# pmic_mt3406_buck.net
KiCad netlist of a schematic drawn in Altium Designer
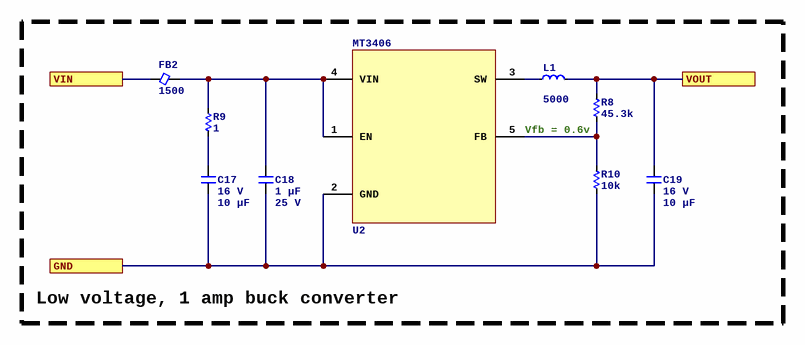
[diagram p0: pmic_mt3406_buck.SchDoc]

(export (version "E")
  (design (tool "Eeschema 10.0.6"))
  (components
    (comp (ref "C17")
      (value "CL21B106KOQNNNE")
      (footprint "C0805")
      (fields
        (field (name "VOLTAGE RATING") "16 V")
        (field (name "CAPACITANCE") "10 µF")
        (field (name "MANUFACTURER") "Samsung Electro-Mechanics")
      )
      (libsource (lib "database") (part "__template_cap"))
    )
    (comp (ref "C18")
      (value "CL10B105KA8NNNC")
      (footprint "C0603")
      (fields
        (field (name "CAPACITANCE") "1 µF")
        (field (name "MANUFACTURER") "Samsung Electro-Mechanics")
        (field (name "VOLTAGE RATING") "25 V")
      )
      (libsource (lib "database") (part "__template_cap"))
    )
    (comp (ref "C19")
      (value "CL21B106KOQNNNE")
      (footprint "C0805")
      (fields
        (field (name "VOLTAGE RATING") "16 V")
        (field (name "CAPACITANCE") "10 µF")
        (field (name "MANUFACTURER") "Samsung Electro-Mechanics")
      )
      (libsource (lib "database") (part "__template_cap"))
    )
    (comp (ref "FB2")
      (value "MPZ2012S102AT000")
      (footprint "FB0805")
      (fields (field (name "CURRENT RATING (MA)") "1500") (field (name "MANUFACTURER") "TDK"))
      (libsource (lib "database") (part "__template_fb"))
    )
    (comp (ref "L1")
      (value "FTC404020S4R7MGCA")
      (footprint "SMD-4.1x4.1x2.0")
      (description "4.7 µH SMD power inductor")
      (fields (field (name "MANUFACTURER") "cjiang") (field (name "CURRENT RATING (MA)") "5000"))
      (libsource (lib "database") (part "__template_inductor"))
    )
    (comp (ref "R8")
      (value "45.3k")
      (footprint "R0402")
      (fields
        (field (name "TOLERANCE") "1%")
        (field (name "MANUFACTURER PART NUMBER") "FRC0402F4532TS")
        (field (name "MANUFACTURER") "FOJAN")
      )
      (libsource (lib "database") (part "__template_resistor"))
    )
    (comp (ref "R9")
      (value "1")
      (footprint "R0402")
      (fields
        (field (name "TOLERANCE") "1%")
        (field (name "MANUFACTURER PART NUMBER") "CRCW04021R00FKEDC")
        (field (name "MANUFACTURER") "Vishay Intertech")
      )
      (libsource (lib "database") (part "__template_resistor"))
    )
    (comp (ref "R10")
      (value "10k")
      (footprint "R0402")
      (fields
        (field (name "TOLERANCE") "1%")
        (field (name "MANUFACTURER PART NUMBER") "0402WGF1002TCE")
        (field (name "MANUFACTURER") "UNI-ROYAL(Uniroyal Elec)")
      )
      (libsource (lib "database") (part "__template_resistor"))
    )
    (comp (ref "U2")
      (value "MT3406")
      (footprint "5SOT23")
      (fields (field (name "MANUFACTURER") "XI'AN Aerosemi Tech"))
      (libsource (lib "database") (part "MT3406"))
    )
  )
  (nets
    (net (code "1") (name "/GND") (class "Default")
      (node (ref "C17") (pin "2") (pintype "passive"))
      (node (ref "C18") (pin "2") (pintype "passive"))
      (node (ref "C19") (pin "2") (pintype "passive"))
      (node (ref "R10") (pin "2") (pintype "passive"))
      (node (ref "U2") (pin "2") (pinfunction "GND_2") (pintype "passive"))
    )
    (net (code "2") (name "/VIN") (class "Default") (node (ref "FB2") (pin "1") (pintype "passive")))
    (net (code "3") (name "/VOUT") (class "Default")
      (node (ref "C19") (pin "1") (pintype "passive"))
      (node (ref "L1") (pin "2") (pintype "passive"))
      (node (ref "R8") (pin "1") (pintype "passive"))
    )
    (net (code "4") (name "Net-(C17-Pad1)") (class "Default")
      (node (ref "C17") (pin "1") (pintype "passive"))
      (node (ref "R9") (pin "1") (pintype "passive"))
    )
    (net (code "5") (name "Net-(U2-EN)") (class "Default")
      (node (ref "C18") (pin "1") (pintype "passive"))
      (node (ref "FB2") (pin "2") (pintype "passive"))
      (node (ref "R9") (pin "2") (pintype "passive"))
      (node (ref "U2") (pin "1") (pinfunction "EN_1") (pintype "passive"))
      (node (ref "U2") (pin "4") (pinfunction "VIN_4") (pintype "passive"))
    )
    (net (code "6") (name "Net-(U2-FB)") (class "Default")
      (node (ref "R10") (pin "1") (pintype "passive"))
      (node (ref "R8") (pin "2") (pintype "passive"))
      (node (ref "U2") (pin "5") (pinfunction "FB_5") (pintype "passive"))
    )
    (net (code "7") (name "Net-(U2-SW)") (class "Default")
      (node (ref "L1") (pin "1") (pintype "passive"))
      (node (ref "U2") (pin "3") (pinfunction "SW_3") (pintype "passive"))
    )
  )
)
